# 03_RPI_VIDEO.net
KiCad netlist of a schematic drawn in Altium Designer
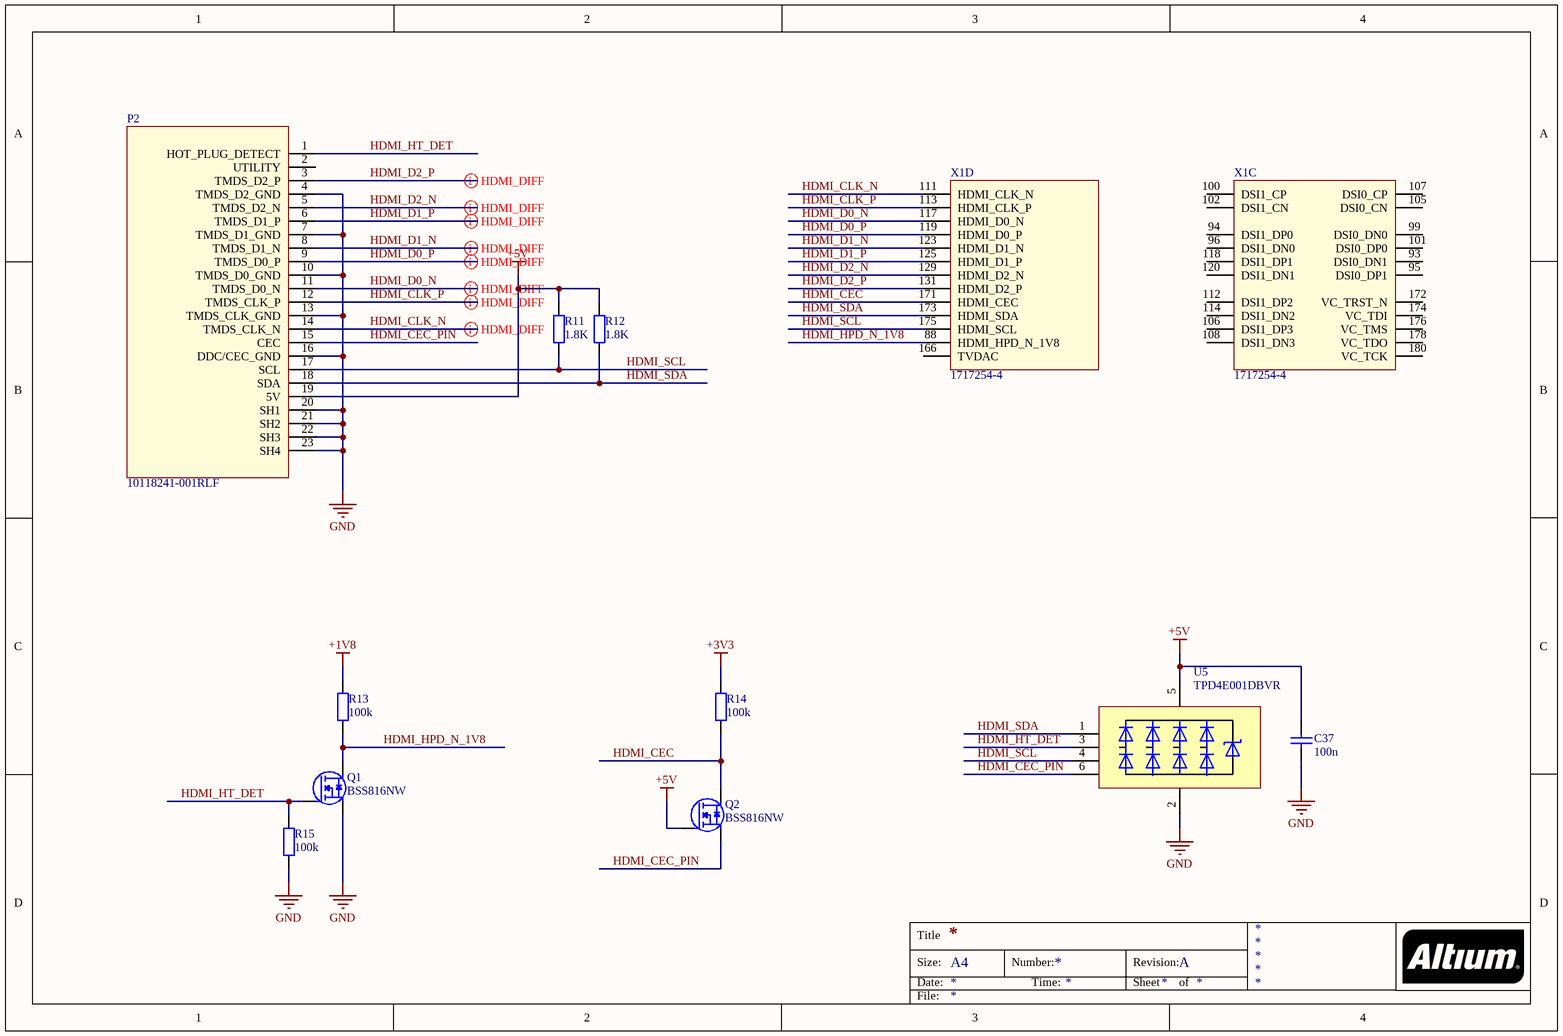
[diagram p0: 03_RPI_VIDEO.SchDoc]

(export (version "E")
  (design (tool "Eeschema 10.0.6"))
  (components
    (comp (ref "C37")
      (value "100n")
      (footprint "C0603_IPC_HD")
      (description "CAP CER 0.1UF 16V X7R 0603")
      (fields
        (field (name "MANUFACTURER") "Samsung Electro-Mechanics")
        (field (name "MANUFACTURER PART NUMBER") "CL10B104KO8NNNC")
      )
      (libsource (lib "alfasat_lib") (part "CL10B104KO8NNNC"))
    )
    (comp (ref "P2")
      (value "10118241-001RLF")
      (footprint "10118241-001RLF")
      (description "CONN RCP MICRO HDMI 19POS SMD RA")
      (fields (field (name "MANUFACTURER") "Amphenol ICC (FCI)"))
      (libsource (lib "alfasat_lib") (part "10118241-001RLF"))
    )
    (comp (ref "Q1")
      (value "BSS816NW")
      (footprint "SOT323")
      (description "N-Channel Logic Level Enhancement Mode Field Effect Transistor")
      (fields (field (name "MANUFACTURER") "Infineon Technologies"))
      (libsource (lib "alfasat_lib") (part "BSS816"))
    )
    (comp (ref "Q2")
      (value "BSS816NW")
      (footprint "SOT323")
      (description "N-Channel Logic Level Enhancement Mode Field Effect Transistor")
      (fields (field (name "MANUFACTURER") "Infineon Technologies"))
      (libsource (lib "alfasat_lib") (part "BSS816"))
    )
    (comp (ref "R11")
      (value "1.8K")
      (footprint "R0603_IPC_MD")
      (description "RES SMD 1.8K OHM 5% 1/10W 0603")
      (fields
        (field (name "MANUFACTURER") "Bourns Inc.")
        (field (name "MANUFACTURER PART NUMBER") "CR0603-JW-182ELF")
      )
      (libsource (lib "alfasat_lib") (part "CR0603-JW-182ELF"))
    )
    (comp (ref "R12")
      (value "1.8K")
      (footprint "R0603_IPC_MD")
      (description "RES SMD 1.8K OHM 5% 1/10W 0603")
      (fields
        (field (name "MANUFACTURER") "Bourns Inc.")
        (field (name "MANUFACTURER PART NUMBER") "CR0603-JW-182ELF")
      )
      (libsource (lib "alfasat_lib") (part "CR0603-JW-182ELF"))
    )
    (comp (ref "R13")
      (value "100k")
      (footprint "R0603_IPC_MD")
      (description "RES 100K OHM 1% 1/10W 0603")
      (fields
        (field (name "MANUFACTURER") "Bourns Inc.")
        (field (name "MANUFACTURER PART NUMBER") "RMCF0603FT100K")
      )
      (libsource (lib "alfasat_lib") (part "RMCF0603FT100K"))
    )
    (comp (ref "R14")
      (value "100k")
      (footprint "R0603_IPC_MD")
      (description "RES 100K OHM 1% 1/10W 0603")
      (fields
        (field (name "MANUFACTURER") "Bourns Inc.")
        (field (name "MANUFACTURER PART NUMBER") "RMCF0603FT100K")
      )
      (libsource (lib "alfasat_lib") (part "RMCF0603FT100K"))
    )
    (comp (ref "R15")
      (value "100k")
      (footprint "R0603_IPC_MD")
      (description "RES 100K OHM 1% 1/10W 0603")
      (fields
        (field (name "MANUFACTURER") "Bourns Inc.")
        (field (name "MANUFACTURER PART NUMBER") "RMCF0603FT100K")
      )
      (libsource (lib "alfasat_lib") (part "RMCF0603FT100K"))
    )
    (comp (ref "U5")
      (value "TPD4E001DBVR")
      (footprint "SOT23-6")
      (description "4x TVS DIODE 5.5V SOT23-6")
      (fields (field (name "MANUFACTURER") "TI"))
      (libsource (lib "alfasat_lib") (part "TPD4E001DBVR"))
    )
    (comp (ref "X1")
      (value "1717254-4")
      (footprint "1717254-1")
      (description "CONN SKT SODIMM 200POS R/A SMD")
      (fields (field (name "MANUFACTURER") "TE Connectivity AMP Connectors"))
      (libsource (lib "alfasat_lib") (part "Raspberry CM Connector"))
    )
  )
  (nets
    (net (code "1") (name "+1V8") (class "Default")
      (node (ref "R13") (pin "2") (pinfunction "2_2") (pintype "passive"))
    )
    (net (code "2") (name "+3V3") (class "Default")
      (node (ref "R14") (pin "2") (pinfunction "2_2") (pintype "passive"))
    )
    (net (code "3") (name "+5V") (class "Default")
      (node (ref "C37") (pin "2") (pinfunction "2_2") (pintype "passive"))
      (node (ref "P2") (pin "19") (pinfunction "5V_19") (pintype "passive"))
      (node (ref "Q2") (pin "1") (pinfunction "G_1") (pintype "passive"))
      (node (ref "R11") (pin "2") (pinfunction "2_2") (pintype "passive"))
      (node (ref "R12") (pin "2") (pinfunction "2_2") (pintype "passive"))
      (node (ref "U5") (pin "5") (pinfunction "VCC_5") (pintype "power_in"))
    )
    (net (code "4") (name "/HDMI_CEC") (class "Default")
      (node (ref "Q2") (pin "3") (pinfunction "D_3") (pintype "passive"))
      (node (ref "R14") (pin "1") (pinfunction "1_1") (pintype "passive"))
      (node (ref "X1") (pin "171") (pinfunction "HDMI_CEC_171") (pintype "passive"))
    )
    (net (code "5") (name "/HDMI_CEC_PIN") (class "Default")
      (node (ref "P2") (pin "15") (pinfunction "CEC_15") (pintype "passive"))
      (node (ref "Q2") (pin "2") (pinfunction "S_2") (pintype "passive"))
      (node (ref "U5") (pin "6") (pinfunction "IO4_6") (pintype "passive"))
    )
    (net (code "6") (name "/HDMI_CLK_N") (class "Default")
      (node (ref "P2") (pin "14") (pinfunction "TMDS_CLK_N_14") (pintype "passive"))
      (node (ref "X1") (pin "111") (pinfunction "HDMI_CLK_N_111") (pintype "passive"))
    )
    (net (code "7") (name "/HDMI_CLK_P") (class "Default")
      (node (ref "P2") (pin "12") (pinfunction "TMDS_CLK_P_12") (pintype "passive"))
      (node (ref "X1") (pin "113") (pinfunction "HDMI_CLK_P_113") (pintype "passive"))
    )
    (net (code "8") (name "/HDMI_D0_N") (class "Default")
      (node (ref "P2") (pin "11") (pinfunction "TMDS_D0_N_11") (pintype "passive"))
      (node (ref "X1") (pin "117") (pinfunction "HDMI_D0_N_117") (pintype "passive"))
    )
    (net (code "9") (name "/HDMI_D0_P") (class "Default")
      (node (ref "P2") (pin "9") (pinfunction "TMDS_D0_P_9") (pintype "passive"))
      (node (ref "X1") (pin "119") (pinfunction "HDMI_D0_P_119") (pintype "passive"))
    )
    (net (code "10") (name "/HDMI_D1_N") (class "Default")
      (node (ref "P2") (pin "8") (pinfunction "TMDS_D1_N_8") (pintype "passive"))
      (node (ref "X1") (pin "123") (pinfunction "HDMI_D1_N_123") (pintype "passive"))
    )
    (net (code "11") (name "/HDMI_D1_P") (class "Default")
      (node (ref "P2") (pin "6") (pinfunction "TMDS_D1_P_6") (pintype "passive"))
      (node (ref "X1") (pin "125") (pinfunction "HDMI_D1_P_125") (pintype "passive"))
    )
    (net (code "12") (name "/HDMI_D2_N") (class "Default")
      (node (ref "P2") (pin "5") (pinfunction "TMDS_D2_N_5") (pintype "passive"))
      (node (ref "X1") (pin "129") (pinfunction "HDMI_D2_N_129") (pintype "passive"))
    )
    (net (code "13") (name "/HDMI_D2_P") (class "Default")
      (node (ref "P2") (pin "3") (pinfunction "TMDS_D2_P_3") (pintype "passive"))
      (node (ref "X1") (pin "131") (pinfunction "HDMI_D2_P_131") (pintype "passive"))
    )
    (net (code "14") (name "/HDMI_HPD_N_1V8") (class "Default")
      (node (ref "Q1") (pin "3") (pinfunction "D_3") (pintype "passive"))
      (node (ref "R13") (pin "1") (pinfunction "1_1") (pintype "passive"))
      (node (ref "X1") (pin "88") (pinfunction "HDMI_HPD_N_1V8_88") (pintype "passive"))
    )
    (net (code "15") (name "/HDMI_HT_DET") (class "Default")
      (node (ref "P2") (pin "1") (pinfunction "HOT_PLUG_DETECT_1") (pintype "passive"))
      (node (ref "Q1") (pin "1") (pinfunction "G_1") (pintype "passive"))
      (node (ref "R15") (pin "2") (pinfunction "2_2") (pintype "passive"))
      (node (ref "U5") (pin "3") (pinfunction "IO2_3") (pintype "passive"))
    )
    (net (code "16") (name "/HDMI_SCL") (class "Default")
      (node (ref "P2") (pin "17") (pinfunction "SCL_17") (pintype "passive"))
      (node (ref "R11") (pin "1") (pinfunction "1_1") (pintype "passive"))
      (node (ref "U5") (pin "4") (pinfunction "IO3_4") (pintype "passive"))
      (node (ref "X1") (pin "175") (pinfunction "HDMI_SCL_175") (pintype "passive"))
    )
    (net (code "17") (name "/HDMI_SDA") (class "Default")
      (node (ref "P2") (pin "18") (pinfunction "SDA_18") (pintype "passive"))
      (node (ref "R12") (pin "1") (pinfunction "1_1") (pintype "passive"))
      (node (ref "U5") (pin "1") (pinfunction "IO1_1") (pintype "passive"))
      (node (ref "X1") (pin "173") (pinfunction "HDMI_SDA_173") (pintype "passive"))
    )
    (net (code "18") (name "GND") (class "Default")
      (node (ref "C37") (pin "1") (pinfunction "1_1") (pintype "passive"))
      (node (ref "P2") (pin "10") (pinfunction "TMDS_D0_GND_10") (pintype "passive"))
      (node (ref "P2") (pin "13") (pinfunction "TMDS_CLK_GND_13") (pintype "passive"))
      (node (ref "P2") (pin "16") (pinfunction "DDC/CEC_GND_16") (pintype "passive"))
      (node (ref "P2") (pin "20") (pinfunction "SH1_20") (pintype "passive"))
      (node (ref "P2") (pin "21") (pinfunction "SH2_21") (pintype "passive"))
      (node (ref "P2") (pin "22") (pinfunction "SH3_22") (pintype "passive"))
      (node (ref "P2") (pin "23") (pinfunction "SH4_23") (pintype "passive"))
      (node (ref "P2") (pin "4") (pinfunction "TMDS_D2_GND_4") (pintype "passive"))
      (node (ref "P2") (pin "7") (pinfunction "TMDS_D1_GND_7") (pintype "passive"))
      (node (ref "Q1") (pin "2") (pinfunction "S_2") (pintype "passive"))
      (node (ref "R15") (pin "1") (pinfunction "1_1") (pintype "passive"))
      (node (ref "U5") (pin "2") (pinfunction "GND_2") (pintype "power_in"))
    )
    (net (code "19") (name "unconnected-(P2-UTILITY-Pad2)") (class "Default")
      (node (ref "P2") (pin "2") (pinfunction "UTILITY_2") (pintype "passive"))
    )
    (net (code "20") (name "unconnected-(X1C-DSI0_CN-Pad105)") (class "Default")
      (node (ref "X1") (pin "105") (pinfunction "DSI0_CN_105") (pintype "passive"))
    )
    (net (code "21") (name "unconnected-(X1C-DSI0_CP-Pad107)") (class "Default")
      (node (ref "X1") (pin "107") (pinfunction "DSI0_CP_107") (pintype "passive"))
    )
    (net (code "22") (name "unconnected-(X1C-DSI0_DN0-Pad99)") (class "Default")
      (node (ref "X1") (pin "99") (pinfunction "DSI0_DN0_99") (pintype "passive"))
    )
    (net (code "23") (name "unconnected-(X1C-DSI0_DN1-Pad93)") (class "Default")
      (node (ref "X1") (pin "93") (pinfunction "DSI0_DN1_93") (pintype "passive"))
    )
    (net (code "24") (name "unconnected-(X1C-DSI0_DP0-Pad101)") (class "Default")
      (node (ref "X1") (pin "101") (pinfunction "DSI0_DP0_101") (pintype "passive"))
    )
    (net (code "25") (name "unconnected-(X1C-DSI0_DP1-Pad95)") (class "Default")
      (node (ref "X1") (pin "95") (pinfunction "DSI0_DP1_95") (pintype "passive"))
    )
    (net (code "26") (name "unconnected-(X1C-DSI1_CN-Pad102)") (class "Default")
      (node (ref "X1") (pin "102") (pinfunction "DSI1_CN_102") (pintype "passive"))
    )
    (net (code "27") (name "unconnected-(X1C-DSI1_CP-Pad100)") (class "Default")
      (node (ref "X1") (pin "100") (pinfunction "DSI1_CP_100") (pintype "passive"))
    )
    (net (code "28") (name "unconnected-(X1C-DSI1_DN0-Pad96)") (class "Default")
      (node (ref "X1") (pin "96") (pinfunction "DSI1_DN0_96") (pintype "passive"))
    )
    (net (code "29") (name "unconnected-(X1C-DSI1_DN1-Pad120)") (class "Default")
      (node (ref "X1") (pin "120") (pinfunction "DSI1_DN1_120") (pintype "passive"))
    )
    (net (code "30") (name "unconnected-(X1C-DSI1_DN2-Pad114)") (class "Default")
      (node (ref "X1") (pin "114") (pinfunction "DSI1_DN2_114") (pintype "passive"))
    )
    (net (code "31") (name "unconnected-(X1C-DSI1_DN3-Pad108)") (class "Default")
      (node (ref "X1") (pin "108") (pinfunction "DSI1_DN3_108") (pintype "passive"))
    )
    (net (code "32") (name "unconnected-(X1C-DSI1_DP0-Pad94)") (class "Default")
      (node (ref "X1") (pin "94") (pinfunction "DSI1_DP0_94") (pintype "passive"))
    )
    (net (code "33") (name "unconnected-(X1C-DSI1_DP1-Pad118)") (class "Default")
      (node (ref "X1") (pin "118") (pinfunction "DSI1_DP1_118") (pintype "passive"))
    )
    (net (code "34") (name "unconnected-(X1C-DSI1_DP2-Pad112)") (class "Default")
      (node (ref "X1") (pin "112") (pinfunction "DSI1_DP2_112") (pintype "passive"))
    )
    (net (code "35") (name "unconnected-(X1C-DSI1_DP3-Pad106)") (class "Default")
      (node (ref "X1") (pin "106") (pinfunction "DSI1_DP3_106") (pintype "passive"))
    )
    (net (code "36") (name "unconnected-(X1C-VC_TCK-Pad180)") (class "Default")
      (node (ref "X1") (pin "180") (pinfunction "VC_TCK_180") (pintype "passive"))
    )
    (net (code "37") (name "unconnected-(X1C-VC_TDI-Pad174)") (class "Default")
      (node (ref "X1") (pin "174") (pinfunction "VC_TDI_174") (pintype "passive"))
    )
    (net (code "38") (name "unconnected-(X1C-VC_TDO-Pad178)") (class "Default")
      (node (ref "X1") (pin "178") (pinfunction "VC_TDO_178") (pintype "passive"))
    )
    (net (code "39") (name "unconnected-(X1C-VC_TMS-Pad176)") (class "Default")
      (node (ref "X1") (pin "176") (pinfunction "VC_TMS_176") (pintype "passive"))
    )
    (net (code "40") (name "unconnected-(X1C-VC_TRST_N-Pad172)") (class "Default")
      (node (ref "X1") (pin "172") (pinfunction "VC_TRST_N_172") (pintype "passive"))
    )
    (net (code "41") (name "unconnected-(X1D-TVDAC-Pad166)") (class "Default")
      (node (ref "X1") (pin "166") (pinfunction "TVDAC_166") (pintype "passive"))
    )
  )
)
